# Protoboard_MX2-8-7.net
KiCad netlist of a schematic drawn in EAGLE
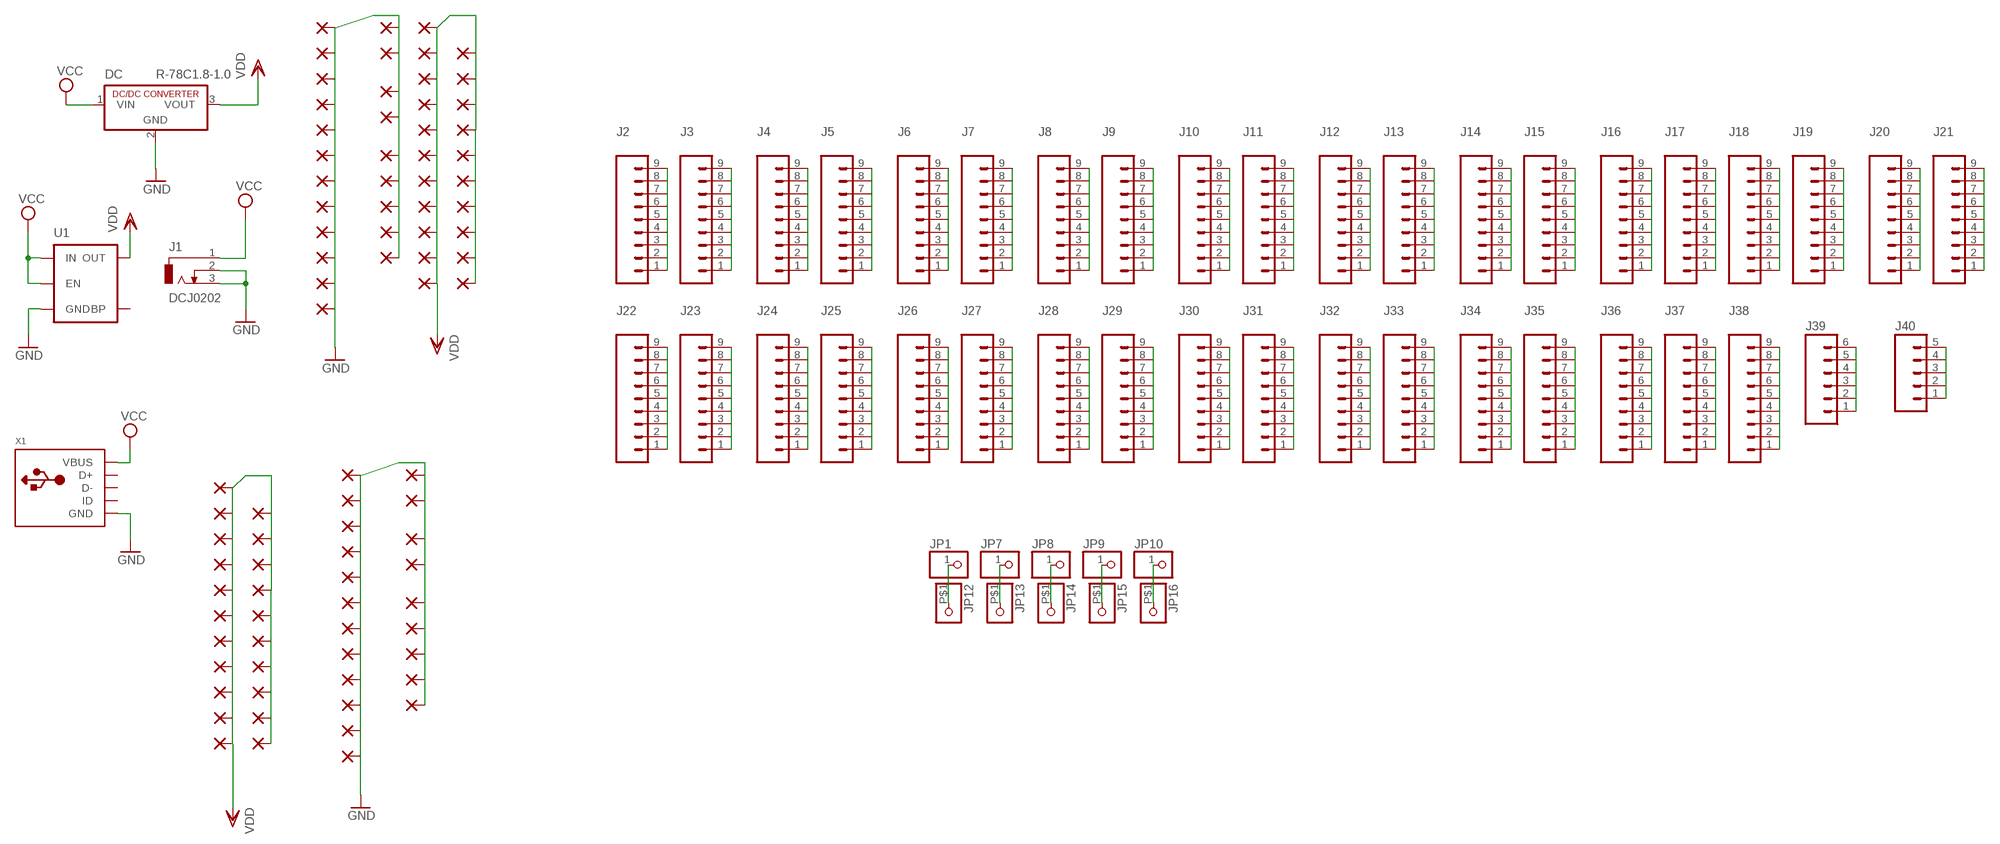
[diagram p0: schematic, sheet 1]

(export (version "E")
  (design (tool "Eeschema 10.0.6"))
  (components
    (comp (ref "DC")
      (value "R-78C1.8-1.0")
      (footprint "eagle-import:SIP3")
      (libsource (lib "eagle-import") (part "R-78C-1.01.8"))
    )
    (comp (ref "J1")
      (value "DCJ0202")
      (footprint "eagle-import:DCJ0202")
      (libsource (lib "eagle-import") (part "DCJ0202"))
    )
    (comp (ref "J2")
      (value "M09NO_SILK")
      (footprint "eagle-import:1X09_NO_SILK")
      (libsource (lib "eagle-import") (part "M09NO_SILK"))
    )
    (comp (ref "J3")
      (value "M09NO_SILK")
      (footprint "eagle-import:1X09_NO_SILK")
      (libsource (lib "eagle-import") (part "M09NO_SILK"))
    )
    (comp (ref "J4")
      (value "M09NO_SILK")
      (footprint "eagle-import:1X09_NO_SILK")
      (libsource (lib "eagle-import") (part "M09NO_SILK"))
    )
    (comp (ref "J5")
      (value "M09NO_SILK")
      (footprint "eagle-import:1X09_NO_SILK")
      (libsource (lib "eagle-import") (part "M09NO_SILK"))
    )
    (comp (ref "J6")
      (value "M09NO_SILK")
      (footprint "eagle-import:1X09_NO_SILK")
      (libsource (lib "eagle-import") (part "M09NO_SILK"))
    )
    (comp (ref "J7")
      (value "M09NO_SILK")
      (footprint "eagle-import:1X09_NO_SILK")
      (libsource (lib "eagle-import") (part "M09NO_SILK"))
    )
    (comp (ref "J8")
      (value "M09NO_SILK")
      (footprint "eagle-import:1X09_NO_SILK")
      (libsource (lib "eagle-import") (part "M09NO_SILK"))
    )
    (comp (ref "J9")
      (value "M09NO_SILK")
      (footprint "eagle-import:1X09_NO_SILK")
      (libsource (lib "eagle-import") (part "M09NO_SILK"))
    )
    (comp (ref "J10")
      (value "M09NO_SILK")
      (footprint "eagle-import:1X09_NO_SILK")
      (libsource (lib "eagle-import") (part "M09NO_SILK"))
    )
    (comp (ref "J11")
      (value "M09NO_SILK")
      (footprint "eagle-import:1X09_NO_SILK")
      (libsource (lib "eagle-import") (part "M09NO_SILK"))
    )
    (comp (ref "J12")
      (value "M09NO_SILK")
      (footprint "eagle-import:1X09_NO_SILK")
      (libsource (lib "eagle-import") (part "M09NO_SILK"))
    )
    (comp (ref "J13")
      (value "M09NO_SILK")
      (footprint "eagle-import:1X09_NO_SILK")
      (libsource (lib "eagle-import") (part "M09NO_SILK"))
    )
    (comp (ref "J14")
      (value "M09NO_SILK")
      (footprint "eagle-import:1X09_NO_SILK")
      (libsource (lib "eagle-import") (part "M09NO_SILK"))
    )
    (comp (ref "J15")
      (value "M09NO_SILK")
      (footprint "eagle-import:1X09_NO_SILK")
      (libsource (lib "eagle-import") (part "M09NO_SILK"))
    )
    (comp (ref "J16")
      (value "M09NO_SILK")
      (footprint "eagle-import:1X09_NO_SILK")
      (libsource (lib "eagle-import") (part "M09NO_SILK"))
    )
    (comp (ref "J17")
      (value "M09NO_SILK")
      (footprint "eagle-import:1X09_NO_SILK")
      (libsource (lib "eagle-import") (part "M09NO_SILK"))
    )
    (comp (ref "J18")
      (value "M09NO_SILK")
      (footprint "eagle-import:1X09_NO_SILK")
      (libsource (lib "eagle-import") (part "M09NO_SILK"))
    )
    (comp (ref "J19")
      (value "M09NO_SILK")
      (footprint "eagle-import:1X09_NO_SILK")
      (libsource (lib "eagle-import") (part "M09NO_SILK"))
    )
    (comp (ref "J20")
      (value "M09NO_SILK")
      (footprint "eagle-import:1X09_NO_SILK")
      (libsource (lib "eagle-import") (part "M09NO_SILK"))
    )
    (comp (ref "J21")
      (value "M09NO_SILK")
      (footprint "eagle-import:1X09_NO_SILK")
      (libsource (lib "eagle-import") (part "M09NO_SILK"))
    )
    (comp (ref "J22")
      (value "M09NO_SILK")
      (footprint "eagle-import:1X09_NO_SILK")
      (libsource (lib "eagle-import") (part "M09NO_SILK"))
    )
    (comp (ref "J23")
      (value "M09NO_SILK")
      (footprint "eagle-import:1X09_NO_SILK")
      (libsource (lib "eagle-import") (part "M09NO_SILK"))
    )
    (comp (ref "J24")
      (value "M09NO_SILK")
      (footprint "eagle-import:1X09_NO_SILK")
      (libsource (lib "eagle-import") (part "M09NO_SILK"))
    )
    (comp (ref "J25")
      (value "M09NO_SILK")
      (footprint "eagle-import:1X09_NO_SILK")
      (libsource (lib "eagle-import") (part "M09NO_SILK"))
    )
    (comp (ref "J26")
      (value "M09NO_SILK")
      (footprint "eagle-import:1X09_NO_SILK")
      (libsource (lib "eagle-import") (part "M09NO_SILK"))
    )
    (comp (ref "J27")
      (value "M09NO_SILK")
      (footprint "eagle-import:1X09_NO_SILK")
      (libsource (lib "eagle-import") (part "M09NO_SILK"))
    )
    (comp (ref "J28")
      (value "M09NO_SILK")
      (footprint "eagle-import:1X09_NO_SILK")
      (libsource (lib "eagle-import") (part "M09NO_SILK"))
    )
    (comp (ref "J29")
      (value "M09NO_SILK")
      (footprint "eagle-import:1X09_NO_SILK")
      (libsource (lib "eagle-import") (part "M09NO_SILK"))
    )
    (comp (ref "J30")
      (value "M09NO_SILK")
      (footprint "eagle-import:1X09_NO_SILK")
      (libsource (lib "eagle-import") (part "M09NO_SILK"))
    )
    (comp (ref "J31")
      (value "M09NO_SILK")
      (footprint "eagle-import:1X09_NO_SILK")
      (libsource (lib "eagle-import") (part "M09NO_SILK"))
    )
    (comp (ref "J32")
      (value "M09NO_SILK")
      (footprint "eagle-import:1X09_NO_SILK")
      (libsource (lib "eagle-import") (part "M09NO_SILK"))
    )
    (comp (ref "J33")
      (value "M09NO_SILK")
      (footprint "eagle-import:1X09_NO_SILK")
      (libsource (lib "eagle-import") (part "M09NO_SILK"))
    )
    (comp (ref "J34")
      (value "M09NO_SILK")
      (footprint "eagle-import:1X09_NO_SILK")
      (libsource (lib "eagle-import") (part "M09NO_SILK"))
    )
    (comp (ref "J35")
      (value "M09NO_SILK")
      (footprint "eagle-import:1X09_NO_SILK")
      (libsource (lib "eagle-import") (part "M09NO_SILK"))
    )
    (comp (ref "J36")
      (value "M09NO_SILK")
      (footprint "eagle-import:1X09_NO_SILK")
      (libsource (lib "eagle-import") (part "M09NO_SILK"))
    )
    (comp (ref "J37")
      (value "M09NO_SILK")
      (footprint "eagle-import:1X09_NO_SILK")
      (libsource (lib "eagle-import") (part "M09NO_SILK"))
    )
    (comp (ref "J38")
      (value "M09NO_SILK")
      (footprint "eagle-import:1X09_NO_SILK")
      (libsource (lib "eagle-import") (part "M09NO_SILK"))
    )
    (comp (ref "J39")
      (value "M06NO_SILK_FEMALE_PTH")
      (footprint "eagle-import:1X06_NO_SILK")
      (libsource (lib "eagle-import") (part "M06NO_SILK_FEMALE_PTH"))
    )
    (comp (ref "J40")
      (value "M05NO_SILK")
      (footprint "eagle-import:1X05_NO_SILK")
      (libsource (lib "eagle-import") (part "M05NO_SILK"))
    )
    (comp (ref "JP1")
      (value "PINHD-1X1CB")
      (footprint "eagle-import:1X01-CLEANBIG")
      (libsource (lib "eagle-import") (part "PINHD-1X1CB"))
    )
    (comp (ref "JP7")
      (value "PINHD-1X1CB")
      (footprint "eagle-import:1X01-CLEANBIG")
      (libsource (lib "eagle-import") (part "PINHD-1X1CB"))
    )
    (comp (ref "JP8")
      (value "PINHD-1X1CB")
      (footprint "eagle-import:1X01-CLEANBIG")
      (libsource (lib "eagle-import") (part "PINHD-1X1CB"))
    )
    (comp (ref "JP9")
      (value "PINHD-1X1CB")
      (footprint "eagle-import:1X01-CLEANBIG")
      (libsource (lib "eagle-import") (part "PINHD-1X1CB"))
    )
    (comp (ref "JP10")
      (value "PINHD-1X1CB")
      (footprint "eagle-import:1X01-CLEANBIG")
      (libsource (lib "eagle-import") (part "PINHD-1X1CB"))
    )
    (comp (ref "JP12")
      (value "PINHD-1X1-BIGPOGO")
      (footprint "eagle-import:1X1-BIGPOGO")
      (libsource (lib "eagle-import") (part "PINHD-1X1-BIGPOGO"))
    )
    (comp (ref "JP13")
      (value "PINHD-1X1-BIGPOGO")
      (footprint "eagle-import:1X1-BIGPOGO")
      (libsource (lib "eagle-import") (part "PINHD-1X1-BIGPOGO"))
    )
    (comp (ref "JP14")
      (value "PINHD-1X1-BIGPOGO")
      (footprint "eagle-import:1X1-BIGPOGO")
      (libsource (lib "eagle-import") (part "PINHD-1X1-BIGPOGO"))
    )
    (comp (ref "JP15")
      (value "PINHD-1X1-BIGPOGO")
      (footprint "eagle-import:1X1-BIGPOGO")
      (libsource (lib "eagle-import") (part "PINHD-1X1-BIGPOGO"))
    )
    (comp (ref "JP16")
      (value "PINHD-1X1-BIGPOGO")
      (footprint "eagle-import:1X1-BIGPOGO")
      (libsource (lib "eagle-import") (part "PINHD-1X1-BIGPOGO"))
    )
    (comp (ref "PAD1")
      (value "1,6/0,8")
      (footprint "eagle-import:1,6_0,8")
      (libsource (lib "eagle-import") (part "1,6/0,8"))
    )
    (comp (ref "PAD2")
      (value "1,6/0,8")
      (footprint "eagle-import:1,6_0,8")
      (libsource (lib "eagle-import") (part "1,6/0,8"))
    )
    (comp (ref "PAD3")
      (value "1,6/0,8")
      (footprint "eagle-import:1,6_0,8")
      (libsource (lib "eagle-import") (part "1,6/0,8"))
    )
    (comp (ref "PAD4")
      (value "1,6/0,8")
      (footprint "eagle-import:1,6_0,8")
      (libsource (lib "eagle-import") (part "1,6/0,8"))
    )
    (comp (ref "PAD5")
      (value "1,6/0,8")
      (footprint "eagle-import:1,6_0,8")
      (libsource (lib "eagle-import") (part "1,6/0,8"))
    )
    (comp (ref "PAD6")
      (value "1,6/0,8")
      (footprint "eagle-import:1,6_0,8")
      (libsource (lib "eagle-import") (part "1,6/0,8"))
    )
    (comp (ref "PAD7")
      (value "1,6/0,8")
      (footprint "eagle-import:1,6_0,8")
      (libsource (lib "eagle-import") (part "1,6/0,8"))
    )
    (comp (ref "PAD8")
      (value "1,6/0,8")
      (footprint "eagle-import:1,6_0,8")
      (libsource (lib "eagle-import") (part "1,6/0,8"))
    )
    (comp (ref "PAD9")
      (value "1,6/0,8")
      (footprint "eagle-import:1,6_0,8")
      (libsource (lib "eagle-import") (part "1,6/0,8"))
    )
    (comp (ref "PAD10")
      (value "1,6/0,8")
      (footprint "eagle-import:1,6_0,8")
      (libsource (lib "eagle-import") (part "1,6/0,8"))
    )
    (comp (ref "PAD11")
      (value "1,6/0,8")
      (footprint "eagle-import:1,6_0,8")
      (libsource (lib "eagle-import") (part "1,6/0,8"))
    )
    (comp (ref "PAD12")
      (value "1,6/0,8")
      (footprint "eagle-import:1,6_0,8")
      (libsource (lib "eagle-import") (part "1,6/0,8"))
    )
    (comp (ref "PAD13")
      (value "1,6/0,8")
      (footprint "eagle-import:1,6_0,8")
      (libsource (lib "eagle-import") (part "1,6/0,8"))
    )
    (comp (ref "PAD14")
      (value "1,6/0,8")
      (footprint "eagle-import:1,6_0,8")
      (libsource (lib "eagle-import") (part "1,6/0,8"))
    )
    (comp (ref "PAD15")
      (value "1,6/0,8")
      (footprint "eagle-import:1,6_0,8")
      (libsource (lib "eagle-import") (part "1,6/0,8"))
    )
    (comp (ref "PAD16")
      (value "1,6/0,8")
      (footprint "eagle-import:1,6_0,8")
      (libsource (lib "eagle-import") (part "1,6/0,8"))
    )
    (comp (ref "PAD17")
      (value "1,6/0,8")
      (footprint "eagle-import:1,6_0,8")
      (libsource (lib "eagle-import") (part "1,6/0,8"))
    )
    (comp (ref "PAD18")
      (value "1,6/0,8")
      (footprint "eagle-import:1,6_0,8")
      (libsource (lib "eagle-import") (part "1,6/0,8"))
    )
    (comp (ref "PAD19")
      (value "1,6/0,8")
      (footprint "eagle-import:1,6_0,8")
      (libsource (lib "eagle-import") (part "1,6/0,8"))
    )
    (comp (ref "PAD22")
      (value "1,6/0,8")
      (footprint "eagle-import:1,6_0,8")
      (libsource (lib "eagle-import") (part "1,6/0,8"))
    )
    (comp (ref "PAD23")
      (value "1,6/0,8")
      (footprint "eagle-import:1,6_0,8")
      (libsource (lib "eagle-import") (part "1,6/0,8"))
    )
    (comp (ref "PAD24")
      (value "1,6/0,8")
      (footprint "eagle-import:1,6_0,8")
      (libsource (lib "eagle-import") (part "1,6/0,8"))
    )
    (comp (ref "PAD25")
      (value "1,6/0,8")
      (footprint "eagle-import:1,6_0,8")
      (libsource (lib "eagle-import") (part "1,6/0,8"))
    )
    (comp (ref "PAD26")
      (value "1,6/0,8")
      (footprint "eagle-import:1,6_0,8")
      (libsource (lib "eagle-import") (part "1,6/0,8"))
    )
    (comp (ref "PAD27")
      (value "1,6/0,8")
      (footprint "eagle-import:1,6_0,8")
      (libsource (lib "eagle-import") (part "1,6/0,8"))
    )
    (comp (ref "PAD28")
      (value "1,6/0,8")
      (footprint "eagle-import:1,6_0,8")
      (libsource (lib "eagle-import") (part "1,6/0,8"))
    )
    (comp (ref "PAD29")
      (value "1,6/0,8")
      (footprint "eagle-import:1,6_0,8")
      (libsource (lib "eagle-import") (part "1,6/0,8"))
    )
    (comp (ref "PAD30")
      (value "1,6/0,8")
      (footprint "eagle-import:1,6_0,8")
      (libsource (lib "eagle-import") (part "1,6/0,8"))
    )
    (comp (ref "PAD31")
      (value "1,6/0,8")
      (footprint "eagle-import:1,6_0,8")
      (libsource (lib "eagle-import") (part "1,6/0,8"))
    )
    (comp (ref "PAD32")
      (value "1,6/0,8")
      (footprint "eagle-import:1,6_0,8")
      (libsource (lib "eagle-import") (part "1,6/0,8"))
    )
    (comp (ref "PAD33")
      (value "1,6/0,8")
      (footprint "eagle-import:1,6_0,8")
      (libsource (lib "eagle-import") (part "1,6/0,8"))
    )
    (comp (ref "PAD34")
      (value "1,6/0,8")
      (footprint "eagle-import:1,6_0,8")
      (libsource (lib "eagle-import") (part "1,6/0,8"))
    )
    (comp (ref "PAD35")
      (value "1,6/0,8")
      (footprint "eagle-import:1,6_0,8")
      (libsource (lib "eagle-import") (part "1,6/0,8"))
    )
    (comp (ref "PAD36")
      (value "1,6/0,8")
      (footprint "eagle-import:1,6_0,8")
      (libsource (lib "eagle-import") (part "1,6/0,8"))
    )
    (comp (ref "PAD37")
      (value "1,6/0,8")
      (footprint "eagle-import:1,6_0,8")
      (libsource (lib "eagle-import") (part "1,6/0,8"))
    )
    (comp (ref "PAD39")
      (value "1,6/0,8")
      (footprint "eagle-import:1,6_0,8")
      (libsource (lib "eagle-import") (part "1,6/0,8"))
    )
    (comp (ref "PAD40")
      (value "1,6/0,8")
      (footprint "eagle-import:1,6_0,8")
      (libsource (lib "eagle-import") (part "1,6/0,8"))
    )
    (comp (ref "PAD41")
      (value "1,6/0,8")
      (footprint "eagle-import:1,6_0,8")
      (libsource (lib "eagle-import") (part "1,6/0,8"))
    )
    (comp (ref "PAD43")
      (value "1,6/0,8")
      (footprint "eagle-import:1,6_0,8")
      (libsource (lib "eagle-import") (part "1,6/0,8"))
    )
    (comp (ref "PAD44")
      (value "1,6/0,8")
      (footprint "eagle-import:1,6_0,8")
      (libsource (lib "eagle-import") (part "1,6/0,8"))
    )
    (comp (ref "PAD45")
      (value "1,6/0,8")
      (footprint "eagle-import:1,6_0,8")
      (libsource (lib "eagle-import") (part "1,6/0,8"))
    )
    (comp (ref "PAD46")
      (value "1,6/0,8")
      (footprint "eagle-import:1,6_0,8")
      (libsource (lib "eagle-import") (part "1,6/0,8"))
    )
    (comp (ref "PAD421")
      (value "1,6/0,8")
      (footprint "eagle-import:1,6_0,8")
      (libsource (lib "eagle-import") (part "1,6/0,8"))
    )
    (comp (ref "PAD422")
      (value "1,6/0,8")
      (footprint "eagle-import:1,6_0,8")
      (libsource (lib "eagle-import") (part "1,6/0,8"))
    )
    (comp (ref "PAD423")
      (value "1,6/0,8")
      (footprint "eagle-import:1,6_0,8")
      (libsource (lib "eagle-import") (part "1,6/0,8"))
    )
    (comp (ref "PAD424")
      (value "1,6/0,8")
      (footprint "eagle-import:1,6_0,8")
      (libsource (lib "eagle-import") (part "1,6/0,8"))
    )
    (comp (ref "PAD425")
      (value "1,6/0,8")
      (footprint "eagle-import:1,6_0,8")
      (libsource (lib "eagle-import") (part "1,6/0,8"))
    )
    (comp (ref "PAD426")
      (value "1,6/0,8")
      (footprint "eagle-import:1,6_0,8")
      (libsource (lib "eagle-import") (part "1,6/0,8"))
    )
    (comp (ref "PAD427")
      (value "1,6/0,8")
      (footprint "eagle-import:1,6_0,8")
      (libsource (lib "eagle-import") (part "1,6/0,8"))
    )
    (comp (ref "PAD428")
      (value "1,6/0,8")
      (footprint "eagle-import:1,6_0,8")
      (libsource (lib "eagle-import") (part "1,6/0,8"))
    )
    (comp (ref "PAD429")
      (value "1,6/0,8")
      (footprint "eagle-import:1,6_0,8")
      (libsource (lib "eagle-import") (part "1,6/0,8"))
    )
    (comp (ref "PAD430")
      (value "1,6/0,8")
      (footprint "eagle-import:1,6_0,8")
      (libsource (lib "eagle-import") (part "1,6/0,8"))
    )
    (comp (ref "PAD431")
      (value "1,6/0,8")
      (footprint "eagle-import:1,6_0,8")
      (libsource (lib "eagle-import") (part "1,6/0,8"))
    )
    (comp (ref "PAD432")
      (value "1,6/0,8")
      (footprint "eagle-import:1,6_0,8")
      (libsource (lib "eagle-import") (part "1,6/0,8"))
    )
    (comp (ref "PAD433")
      (value "1,6/0,8")
      (footprint "eagle-import:1,6_0,8")
      (libsource (lib "eagle-import") (part "1,6/0,8"))
    )
    (comp (ref "PAD434")
      (value "1,6/0,8")
      (footprint "eagle-import:1,6_0,8")
      (libsource (lib "eagle-import") (part "1,6/0,8"))
    )
    (comp (ref "PAD435")
      (value "1,6/0,8")
      (footprint "eagle-import:1,6_0,8")
      (libsource (lib "eagle-import") (part "1,6/0,8"))
    )
    (comp (ref "PAD436")
      (value "1,6/0,8")
      (footprint "eagle-import:1,6_0,8")
      (libsource (lib "eagle-import") (part "1,6/0,8"))
    )
    (comp (ref "PAD437")
      (value "1,6/0,8")
      (footprint "eagle-import:1,6_0,8")
      (libsource (lib "eagle-import") (part "1,6/0,8"))
    )
    (comp (ref "PAD438")
      (value "1,6/0,8")
      (footprint "eagle-import:1,6_0,8")
      (libsource (lib "eagle-import") (part "1,6/0,8"))
    )
    (comp (ref "PAD439")
      (value "1,6/0,8")
      (footprint "eagle-import:1,6_0,8")
      (libsource (lib "eagle-import") (part "1,6/0,8"))
    )
    (comp (ref "PAD440")
      (value "1,6/0,8")
      (footprint "eagle-import:1,6_0,8")
      (libsource (lib "eagle-import") (part "1,6/0,8"))
    )
    (comp (ref "PAD441")
      (value "1,6/0,8")
      (footprint "eagle-import:1,6_0,8")
      (libsource (lib "eagle-import") (part "1,6/0,8"))
    )
    (comp (ref "PAD442")
      (value "1,6/0,8")
      (footprint "eagle-import:1,6_0,8")
      (libsource (lib "eagle-import") (part "1,6/0,8"))
    )
    (comp (ref "PAD443")
      (value "1,6/0,8")
      (footprint "eagle-import:1,6_0,8")
      (libsource (lib "eagle-import") (part "1,6/0,8"))
    )
    (comp (ref "PAD444")
      (value "1,6/0,8")
      (footprint "eagle-import:1,6_0,8")
      (libsource (lib "eagle-import") (part "1,6/0,8"))
    )
    (comp (ref "PAD445")
      (value "1,6/0,8")
      (footprint "eagle-import:1,6_0,8")
      (libsource (lib "eagle-import") (part "1,6/0,8"))
    )
    (comp (ref "PAD446")
      (value "1,6/0,8")
      (footprint "eagle-import:1,6_0,8")
      (libsource (lib "eagle-import") (part "1,6/0,8"))
    )
    (comp (ref "PAD447")
      (value "1,6/0,8")
      (footprint "eagle-import:1,6_0,8")
      (libsource (lib "eagle-import") (part "1,6/0,8"))
    )
    (comp (ref "PAD448")
      (value "1,6/0,8")
      (footprint "eagle-import:1,6_0,8")
      (libsource (lib "eagle-import") (part "1,6/0,8"))
    )
    (comp (ref "PAD449")
      (value "1,6/0,8")
      (footprint "eagle-import:1,6_0,8")
      (libsource (lib "eagle-import") (part "1,6/0,8"))
    )
    (comp (ref "PAD450")
      (value "1,6/0,8")
      (footprint "eagle-import:1,6_0,8")
      (libsource (lib "eagle-import") (part "1,6/0,8"))
    )
    (comp (ref "PAD451")
      (value "1,6/0,8")
      (footprint "eagle-import:1,6_0,8")
      (libsource (lib "eagle-import") (part "1,6/0,8"))
    )
    (comp (ref "PAD452")
      (value "1,6/0,8")
      (footprint "eagle-import:1,6_0,8")
      (libsource (lib "eagle-import") (part "1,6/0,8"))
    )
    (comp (ref "PAD453")
      (value "1,6/0,8")
      (footprint "eagle-import:1,6_0,8")
      (libsource (lib "eagle-import") (part "1,6/0,8"))
    )
    (comp (ref "PAD454")
      (value "1,6/0,8")
      (footprint "eagle-import:1,6_0,8")
      (libsource (lib "eagle-import") (part "1,6/0,8"))
    )
    (comp (ref "PAD455")
      (value "1,6/0,8")
      (footprint "eagle-import:1,6_0,8")
      (libsource (lib "eagle-import") (part "1,6/0,8"))
    )
    (comp (ref "PAD456")
      (value "1,6/0,8")
      (footprint "eagle-import:1,6_0,8")
      (libsource (lib "eagle-import") (part "1,6/0,8"))
    )
    (comp (ref "PAD457")
      (value "1,6/0,8")
      (footprint "eagle-import:1,6_0,8")
      (libsource (lib "eagle-import") (part "1,6/0,8"))
    )
    (comp (ref "PAD458")
      (value "1,6/0,8")
      (footprint "eagle-import:1,6_0,8")
      (libsource (lib "eagle-import") (part "1,6/0,8"))
    )
    (comp (ref "PAD459")
      (value "1,6/0,8")
      (footprint "eagle-import:1,6_0,8")
      (libsource (lib "eagle-import") (part "1,6/0,8"))
    )
    (comp (ref "PAD460")
      (value "1,6/0,8")
      (footprint "eagle-import:1,6_0,8")
      (libsource (lib "eagle-import") (part "1,6/0,8"))
    )
    (comp (ref "PAD461")
      (value "1,6/0,8")
      (footprint "eagle-import:1,6_0,8")
      (libsource (lib "eagle-import") (part "1,6/0,8"))
    )
    (comp (ref "PAD462")
      (value "1,6/0,8")
      (footprint "eagle-import:1,6_0,8")
      (libsource (lib "eagle-import") (part "1,6/0,8"))
    )
    (comp (ref "U1")
      (value "MIC52053.3V")
      (footprint "eagle-import:SOT23-5")
      (libsource (lib "eagle-import") (part "MIC52053.3V"))
    )
    (comp (ref "X1")
      (value "USB_MICRO_20329_V2")
      (footprint "eagle-import:4UCONN_20329_V2")
      (libsource (lib "eagle-import") (part "USB_MICRO_20329_V2"))
    )
  )
  (nets
    (net (code "1") (name "GND") (class "Default")
      (node (ref "DC") (pin "2") (pinfunction "GND_2") (pintype "passive"))
      (node (ref "J1") (pin "2") (pinfunction "2_2") (pintype "passive"))
      (node (ref "J1") (pin "3") (pinfunction "3_3") (pintype "passive"))
      (node (ref "PAD1") (pin "1") (pinfunction "P_1") (pintype "passive"))
      (node (ref "PAD10") (pin "1") (pinfunction "P_1") (pintype "passive"))
      (node (ref "PAD11") (pin "1") (pinfunction "P_1") (pintype "passive"))
      (node (ref "PAD12") (pin "1") (pinfunction "P_1") (pintype "passive"))
      (node (ref "PAD13") (pin "1") (pinfunction "P_1") (pintype "passive"))
      (node (ref "PAD14") (pin "1") (pinfunction "P_1") (pintype "passive"))
      (node (ref "PAD16") (pin "1") (pinfunction "P_1") (pintype "passive"))
      (node (ref "PAD17") (pin "1") (pinfunction "P_1") (pintype "passive"))
      (node (ref "PAD18") (pin "1") (pinfunction "P_1") (pintype "passive"))
      (node (ref "PAD19") (pin "1") (pinfunction "P_1") (pintype "passive"))
      (node (ref "PAD2") (pin "1") (pinfunction "P_1") (pintype "passive"))
      (node (ref "PAD22") (pin "1") (pinfunction "P_1") (pintype "passive"))
      (node (ref "PAD23") (pin "1") (pinfunction "P_1") (pintype "passive"))
      (node (ref "PAD24") (pin "1") (pinfunction "P_1") (pintype "passive"))
      (node (ref "PAD3") (pin "1") (pinfunction "P_1") (pintype "passive"))
      (node (ref "PAD4") (pin "1") (pinfunction "P_1") (pintype "passive"))
      (node (ref "PAD421") (pin "1") (pinfunction "P_1") (pintype "passive"))
      (node (ref "PAD422") (pin "1") (pinfunction "P_1") (pintype "passive"))
      (node (ref "PAD423") (pin "1") (pinfunction "P_1") (pintype "passive"))
      (node (ref "PAD424") (pin "1") (pinfunction "P_1") (pintype "passive"))
      (node (ref "PAD425") (pin "1") (pinfunction "P_1") (pintype "passive"))
      (node (ref "PAD426") (pin "1") (pinfunction "P_1") (pintype "passive"))
      (node (ref "PAD427") (pin "1") (pinfunction "P_1") (pintype "passive"))
      (node (ref "PAD428") (pin "1") (pinfunction "P_1") (pintype "passive"))
      (node (ref "PAD429") (pin "1") (pinfunction "P_1") (pintype "passive"))
      (node (ref "PAD430") (pin "1") (pinfunction "P_1") (pintype "passive"))
      (node (ref "PAD431") (pin "1") (pinfunction "P_1") (pintype "passive"))
      (node (ref "PAD432") (pin "1") (pinfunction "P_1") (pintype "passive"))
      (node (ref "PAD433") (pin "1") (pinfunction "P_1") (pintype "passive"))
      (node (ref "PAD434") (pin "1") (pinfunction "P_1") (pintype "passive"))
      (node (ref "PAD435") (pin "1") (pinfunction "P_1") (pintype "passive"))
      (node (ref "PAD436") (pin "1") (pinfunction "P_1") (pintype "passive"))
      (node (ref "PAD437") (pin "1") (pinfunction "P_1") (pintype "passive"))
      (node (ref "PAD438") (pin "1") (pinfunction "P_1") (pintype "passive"))
      (node (ref "PAD439") (pin "1") (pinfunction "P_1") (pintype "passive"))
      (node (ref "PAD440") (pin "1") (pinfunction "P_1") (pintype "passive"))
      (node (ref "PAD441") (pin "1") (pinfunction "P_1") (pintype "passive"))
      (node (ref "PAD5") (pin "1") (pinfunction "P_1") (pintype "passive"))
      (node (ref "PAD6") (pin "1") (pinfunction "P_1") (pintype "passive"))
      (node (ref "PAD7") (pin "1") (pinfunction "P_1") (pintype "passive"))
      (node (ref "PAD8") (pin "1") (pinfunction "P_1") (pintype "passive"))
      (node (ref "PAD9") (pin "1") (pinfunction "P_1") (pintype "passive"))
      (node (ref "U1") (pin "2") (pinfunction "GND_2") (pintype "input"))
      (node (ref "X1") (pin "BASE@1") (pinfunction "GND_BASE@1") (pintype "power_in"))
      (node (ref "X1") (pin "BASE@2") (pinfunction "GND_BASE@2") (pintype "power_in"))
      (node (ref "X1") (pin "GND") (pinfunction "GND_GND") (pintype "power_in"))
      (node (ref "X1") (pin "SPRT@1") (pinfunction "GND_SPRT@1") (pintype "power_in"))
      (node (ref "X1") (pin "SPRT@2") (pinfunction "GND_SPRT@2") (pintype "power_in"))
      (node (ref "X1") (pin "SPRT@3") (pinfunction "GND_SPRT@3") (pintype "power_in"))
      (node (ref "X1") (pin "SPRT@4") (pinfunction "GND_SPRT@4") (pintype "power_in"))
    )
    (net (code "2") (name "Net-(J2-Pad1)") (class "Default")
      (node (ref "J2") (pin "1") (pinfunction "1_1") (pintype "passive"))
      (node (ref "J2") (pin "2") (pinfunction "2_2") (pintype "passive"))
      (node (ref "J2") (pin "3") (pinfunction "3_3") (pintype "passive"))
      (node (ref "J2") (pin "4") (pinfunction "4_4") (pintype "passive"))
      (node (ref "J2") (pin "5") (pinfunction "5_5") (pintype "passive"))
      (node (ref "J2") (pin "6") (pinfunction "6_6") (pintype "passive"))
      (node (ref "J2") (pin "7") (pinfunction "7_7") (pintype "passive"))
      (node (ref "J2") (pin "8") (pinfunction "8_8") (pintype "passive"))
      (node (ref "J2") (pin "9") (pinfunction "9_9") (pintype "passive"))
    )
    (net (code "3") (name "Net-(J3-Pad1)") (class "Default")
      (node (ref "J3") (pin "1") (pinfunction "1_1") (pintype "passive"))
      (node (ref "J3") (pin "2") (pinfunction "2_2") (pintype "passive"))
      (node (ref "J3") (pin "3") (pinfunction "3_3") (pintype "passive"))
      (node (ref "J3") (pin "4") (pinfunction "4_4") (pintype "passive"))
      (node (ref "J3") (pin "5") (pinfunction "5_5") (pintype "passive"))
      (node (ref "J3") (pin "6") (pinfunction "6_6") (pintype "passive"))
      (node (ref "J3") (pin "7") (pinfunction "7_7") (pintype "passive"))
      (node (ref "J3") (pin "8") (pinfunction "8_8") (pintype "passive"))
      (node (ref "J3") (pin "9") (pinfunction "9_9") (pintype "passive"))
    )
    (net (code "4") (name "Net-(J4-Pad1)") (class "Default")
      (node (ref "J4") (pin "1") (pinfunction "1_1") (pintype "passive"))
      (node (ref "J4") (pin "2") (pinfunction "2_2") (pintype "passive"))
      (node (ref "J4") (pin "3") (pinfunction "3_3") (pintype "passive"))
      (node (ref "J4") (pin "4") (pinfunction "4_4") (pintype "passive"))
      (node (ref "J4") (pin "5") (pinfunction "5_5") (pintype "passive"))
      (node (ref "J4") (pin "6") (pinfunction "6_6") (pintype "passive"))
      (node (ref "J4") (pin "7") (pinfunction "7_7") (pintype "passive"))
      (node (ref "J4") (pin "8") (pinfunction "8_8") (pintype "passive"))
      (node (ref "J4") (pin "9") (pinfunction "9_9") (pintype "passive"))
    )
    (net (code "5") (name "Net-(J5-Pad1)") (class "Default")
      (node (ref "J5") (pin "1") (pinfunction "1_1") (pintype "passive"))
      (node (ref "J5") (pin "2") (pinfunction "2_2") (pintype "passive"))
      (node (ref "J5") (pin "3") (pinfunction "3_3") (pintype "passive"))
      (node (ref "J5") (pin "4") (pinfunction "4_4") (pintype "passive"))
      (node (ref "J5") (pin "5") (pinfunction "5_5") (pintype "passive"))
      (node (ref "J5") (pin "6") (pinfunction "6_6") (pintype "passive"))
      (node (ref "J5") (pin "7") (pinfunction "7_7") (pintype "passive"))
      (node (ref "J5") (pin "8") (pinfunction "8_8") (pintype "passive"))
      (node (ref "J5") (pin "9") (pinfunction "9_9") (pintype "passive"))
    )
    (net (code "6") (name "Net-(J6-Pad1)") (class "Default")
      (node (ref "J6") (pin "1") (pinfunction "1_1") (pintype "passive"))
      (node (ref "J6") (pin "2") (pinfunction "2_2") (pintype "passive"))
      (node (ref "J6") (pin "3") (pinfunction "3_3") (pintype "passive"))
      (node (ref "J6") (pin "4") (pinfunction "4_4") (pintype "passive"))
      (node (ref "J6") (pin "5") (pinfunction "5_5") (pintype "passive"))
      (node (ref "J6") (pin "6") (pinfunction "6_6") (pintype "passive"))
      (node (ref "J6") (pin "7") (pinfunction "7_7") (pintype "passive"))
      (node (ref "J6") (pin "8") (pinfunction "8_8") (pintype "passive"))
      (node (ref "J6") (pin "9") (pinfunction "9_9") (pintype "passive"))
    )
    (net (code "7") (name "Net-(J7-Pad1)") (class "Default")
      (node (ref "J7") (pin "1") (pinfunction "1_1") (pintype "passive"))
      (node (ref "J7") (pin "2") (pinfunction "2_2") (pintype "passive"))
      (node (ref "J7") (pin "3") (pinfunction "3_3") (pintype "passive"))
      (node (ref "J7") (pin "4") (pinfunction "4_4") (pintype "passive"))
      (node (ref "J7") (pin "5") (pinfunction "5_5") (pintype "passive"))
      (node (ref "J7") (pin "6") (pinfunction "6_6") (pintype "passive"))
      (node (ref "J7") (pin "7") (pinfunction "7_7") (pintype "passive"))
      (node (ref "J7") (pin "8") (pinfunction "8_8") (pintype "passive"))
      (node (ref "J7") (pin "9") (pinfunction "9_9") (pintype "passive"))
    )
    (net (code "8") (name "Net-(J8-Pad1)") (class "Default")
      (node (ref "J8") (pin "1") (pinfunction "1_1") (pintype "passive"))
      (node (ref "J8") (pin "2") (pinfunction "2_2") (pintype "passive"))
      (node (ref "J8") (pin "3") (pinfunction "3_3") (pintype "passive"))
      (node (ref "J8") (pin "4") (pinfunction "4_4") (pintype "passive"))
      (node (ref "J8") (pin "5") (pinfunction "5_5") (pintype "passive"))
      (node (ref "J8") (pin "6") (pinfunction "6_6") (pintype "passive"))
      (node (ref "J8") (pin "7") (pinfunction "7_7") (pintype "passive"))
      (node (ref "J8") (pin "8") (pinfunction "8_8") (pintype "passive"))
      (node (ref "J8") (pin "9") (pinfunction "9_9") (pintype "passive"))
    )
    (net (code "9") (name "Net-(J9-Pad1)") (class "Default")
      (node (ref "J9") (pin "1") (pinfunction "1_1") (pintype "passive"))
      (node (ref "J9") (pin "2") (pinfunction "2_2") (pintype "passive"))
      (node (ref "J9") (pin "3") (pinfunction "3_3") (pintype "passive"))
      (node (ref "J9") (pin "4") (pinfunction "4_4") (pintype "passive"))
      (node (ref "J9") (pin "5") (pinfunction "5_5") (pintype "passive"))
      (node (ref "J9") (pin "6") (pinfunction "6_6") (pintype "passive"))
      (node (ref "J9") (pin "7") (pinfunction "7_7") (pintype "passive"))
      (node (ref "J9") (pin "8") (pinfunction "8_8") (pintype "passive"))
      (node (ref "J9") (pin "9") (pinfunction "9_9") (pintype "passive"))
    )
    (net (code "10") (name "Net-(J10-Pad1)") (class "Default")
      (node (ref "J10") (pin "1") (pinfunction "1_1") (pintype "passive"))
      (node (ref "J10") (pin "2") (pinfunction "2_2") (pintype "passive"))
      (node (ref "J10") (pin "3") (pinfunction "3_3") (pintype "passive"))
      (node (ref "J10") (pin "4") (pinfunction "4_4") (pintype "passive"))
      (node (ref "J10") (pin "5") (pinfunction "5_5") (pintype "passive"))
      (node (ref "J10") (pin "6") (pinfunction "6_6") (pintype "passive"))
      (node (ref "J10") (pin "7") (pinfunction "7_7") (pintype "passive"))
      (node (ref "J10") (pin "8") (pinfunction "8_8") (pintype "passive"))
      (node (ref "J10") (pin "9") (pinfunction "9_9") (pintype "passive"))
    )
    (net (code "11") (name "Net-(J11-Pad1)") (class "Default")
      (node (ref "J11") (pin "1") (pinfunction "1_1") (pintype "passive"))
      (node (ref "J11") (pin "2") (pinfunction "2_2") (pintype "passive"))
      (node (ref "J11") (pin "3") (pinfunction "3_3") (pintype "passive"))
      (node (ref "J11") (pin "4") (pinfunction "4_4") (pintype "passive"))
      (node (ref "J11") (pin "5") (pinfunction "5_5") (pintype "passive"))
      (node (ref "J11") (pin "6") (pinfunction "6_6") (pintype "passive"))
      (node (ref "J11") (pin "7") (pinfunction "7_7") (pintype "passive"))
      (node (ref "J11") (pin "8") (pinfunction "8_8") (pintype "passive"))
      (node (ref "J11") (pin "9") (pinfunction "9_9") (pintype "passive"))
    )
    (net (code "12") (name "Net-(J12-Pad1)") (class "Default")
      (node (ref "J12") (pin "1") (pinfunction "1_1") (pintype "passive"))
      (node (ref "J12") (pin "2") (pinfunction "2_2") (pintype "passive"))
      (node (ref "J12") (pin "3") (pinfunction "3_3") (pintype "passive"))
      (node (ref "J12") (pin "4") (pinfunction "4_4") (pintype "passive"))
      (node (ref "J12") (pin "5") (pinfunction "5_5") (pintype "passive"))
      (node (ref "J12") (pin "6") (pinfunction "6_6") (pintype "passive"))
      (node (ref "J12") (pin "7") (pinfunction "7_7") (pintype "passive"))
      (node (ref "J12") (pin "8") (pinfunction "8_8") (pintype "passive"))
      (node (ref "J12") (pin "9") (pinfunction "9_9") (pintype "passive"))
    )
    (net (code "13") (name "Net-(J13-Pad1)") (class "Default")
      (node (ref "J13") (pin "1") (pinfunction "1_1") (pintype "passive"))
      (node (ref "J13") (pin "2") (pinfunction "2_2") (pintype "passive"))
      (node (ref "J13") (pin "3") (pinfunction "3_3") (pintype "passive"))
      (node (ref "J13") (pin "4") (pinfunction "4_4") (pintype "passive"))
      (node (ref "J13") (pin "5") (pinfunction "5_5") (pintype "passive"))
      (node (ref "J13") (pin "6") (pinfunction "6_6") (pintype "passive"))
      (node (ref "J13") (pin "7") (pinfunction "7_7") (pintype "passive"))
      (node (ref "J13") (pin "8") (pinfunction "8_8") (pintype "passive"))
      (node (ref "J13") (pin "9") (pinfunction "9_9") (pintype "passive"))
    )
    (net (code "14") (name "Net-(J14-Pad1)") (class "Default")
      (node (ref "J14") (pin "1") (pinfunction "1_1") (pintype "passive"))
      (node (ref "J14") (pin "2") (pinfunction "2_2") (pintype "passive"))
      (node (ref "J14") (pin "3") (pinfunction "3_3") (pintype "passive"))
      (node (ref "J14") (pin "4") (pinfunction "4_4") (pintype "passive"))
      (node (ref "J14") (pin "5") (pinfunction "5_5") (pintype "passive"))
      (node (ref "J14") (pin "6") (pinfunction "6_6") (pintype "passive"))
      (node (ref "J14") (pin "7") (pinfunction "7_7") (pintype "passive"))
      (node (ref "J14") (pin "8") (pinfunction "8_8") (pintype "passive"))
      (node (ref "J14") (pin "9") (pinfunction "9_9") (pintype "passive"))
    )
    (net (code "15") (name "Net-(J15-Pad1)") (class "Default")
      (node (ref "J15") (pin "1") (pinfunction "1_1") (pintype "passive"))
      (node (ref "J15") (pin "2") (pinfunction "2_2") (pintype "passive"))
      (node (ref "J15") (pin "3") (pinfunction "3_3") (pintype "passive"))
      (node (ref "J15") (pin "4") (pinfunction "4_4") (pintype "passive"))
      (node (ref "J15") (pin "5") (pinfunction "5_5") (pintype "passive"))
      (node (ref "J15") (pin "6") (pinfunction "6_6") (pintype "passive"))
      (node (ref "J15") (pin "7") (pinfunction "7_7") (pintype "passive"))
      (node (ref "J15") (pin "8") (pinfunction "8_8") (pintype "passive"))
      (node (ref "J15") (pin "9") (pinfunction "9_9") (pintype "passive"))
    )
    (net (code "16") (name "Net-(J16-Pad1)") (class "Default")
      (node (ref "J16") (pin "1") (pinfunction "1_1") (pintype "passive"))
      (node (ref "J16") (pin "2") (pinfunction "2_2") (pintype "passive"))
      (node (ref "J16") (pin "3") (pinfunction "3_3") (pintype "passive"))
      (node (ref "J16") (pin "4") (pinfunction "4_4") (pintype "passive"))
      (node (ref "J16") (pin "5") (pinfunction "5_5") (pintype "passive"))
      (node (ref "J16") (pin "6") (pinfunction "6_6") (pintype "passive"))
      (node (ref "J16") (pin "7") (pinfunction "7_7") (pintype "passive"))
      (node (ref "J16") (pin "8") (pinfunction "8_8") (pintype "passive"))
      (node (ref "J16") (pin "9") (pinfunction "9_9") (pintype "passive"))
    )
    (net (code "17") (name "Net-(J17-Pad1)") (class "Default")
      (node (ref "J17") (pin "1") (pinfunction "1_1") (pintype "passive"))
      (node (ref "J17") (pin "2") (pinfunction "2_2") (pintype "passive"))
      (node (ref "J17") (pin "3") (pinfunction "3_3") (pintype "passive"))
      (node (ref "J17") (pin "4") (pinfunction "4_4") (pintype "passive"))
      (node (ref "J17") (pin "5") (pinfunction "5_5") (pintype "passive"))
      (node (ref "J17") (pin "6") (pinfunction "6_6") (pintype "passive"))
      (node (ref "J17") (pin "7") (pinfunction "7_7") (pintype "passive"))
      (node (ref "J17") (pin "8") (pinfunction "8_8") (pintype "passive"))
      (node (ref "J17") (pin "9") (pinfunction "9_9") (pintype "passive"))
    )
    (net (code "18") (name "Net-(J18-Pad1)") (class "Default")
      (node (ref "J18") (pin "1") (pinfunction "1_1") (pintype "passive"))
      (node (ref "J18") (pin "2") (pinfunction "2_2") (pintype "passive"))
      (node (ref "J18") (pin "3") (pinfunction "3_3") (pintype "passive"))
      (node (ref "J18") (pin "4") (pinfunction "4_4") (pintype "passive"))
      (node (ref "J18") (pin "5") (pinfunction "5_5") (pintype "passive"))
      (node (ref "J18") (pin "6") (pinfunction "6_6") (pintype "passive"))
      (node (ref "J18") (pin "7") (pinfunction "7_7") (pintype "passive"))
      (node (ref "J18") (pin "8") (pinfunction "8_8") (pintype "passive"))
      (node (ref "J18") (pin "9") (pinfunction "9_9") (pintype "passive"))
    )
    (net (code "19") (name "Net-(J19-Pad1)") (class "Default")
      (node (ref "J19") (pin "1") (pinfunction "1_1") (pintype "passive"))
      (node (ref "J19") (pin "2") (pinfunction "2_2") (pintype "passive"))
      (node (ref "J19") (pin "3") (pinfunction "3_3") (pintype "passive"))
      (node (ref "J19") (pin "4") (pinfunction "4_4") (pintype "passive"))
      (node (ref "J19") (pin "5") (pinfunction "5_5") (pintype "passive"))
      (node (ref "J19") (pin "6") (pinfunction "6_6") (pintype "passive"))
      (node (ref "J19") (pin "7") (pinfunction "7_7") (pintype "passive"))
      (node (ref "J19") (pin "8") (pinfunction "8_8") (pintype "passive"))
      (node (ref "J19") (pin "9") (pinfunction "9_9") (pintype "passive"))
    )
    (net (code "20") (name "Net-(J20-Pad1)") (class "Default")
      (node (ref "J20") (pin "1") (pinfunction "1_1") (pintype "passive"))
      (node (ref "J20") (pin "2") (pinfunction "2_2") (pintype "passive"))
      (node (ref "J20") (pin "3") (pinfunction "3_3") (pintype "passive"))
      (node (ref "J20") (pin "4") (pinfunction "4_4") (pintype "passive"))
      (node (ref "J20") (pin "5") (pinfunction "5_5") (pintype "passive"))
      (node (ref "J20") (pin "6") (pinfunction "6_6") (pintype "passive"))
      (node (ref "J20") (pin "7") (pinfunction "7_7") (pintype "passive"))
      (node (ref "J20") (pin "8") (pinfunction "8_8") (pintype "passive"))
      (node (ref "J20") (pin "9") (pinfunction "9_9") (pintype "passive"))
    )
    (net (code "21") (name "Net-(J21-Pad1)") (class "Default")
      (node (ref "J21") (pin "1") (pinfunction "1_1") (pintype "passive"))
      (node (ref "J21") (pin "2") (pinfunction "2_2") (pintype "passive"))
      (node (ref "J21") (pin "3") (pinfunction "3_3") (pintype "passive"))
      (node (ref "J21") (pin "4") (pinfunction "4_4") (pintype "passive"))
      (node (ref "J21") (pin "5") (pinfunction "5_5") (pintype "passive"))
      (node (ref "J21") (pin "6") (pinfunction "6_6") (pintype "passive"))
      (node (ref "J21") (pin "7") (pinfunction "7_7") (pintype "passive"))
      (node (ref "J21") (pin "8") (pinfunction "8_8") (pintype "passive"))
      (node (ref "J21") (pin "9") (pinfunction "9_9") (pintype "passive"))
    )
    (net (code "22") (name "Net-(J22-Pad1)") (class "Default")
      (node (ref "J22") (pin "1") (pinfunction "1_1") (pintype "passive"))
      (node (ref "J22") (pin "2") (pinfunction "2_2") (pintype "passive"))
      (node (ref "J22") (pin "3") (pinfunction "3_3") (pintype "passive"))
      (node (ref "J22") (pin "4") (pinfunction "4_4") (pintype "passive"))
      (node (ref "J22") (pin "5") (pinfunction "5_5") (pintype "passive"))
      (node (ref "J22") (pin "6") (pinfunction "6_6") (pintype "passive"))
      (node (ref "J22") (pin "7") (pinfunction "7_7") (pintype "passive"))
      (node (ref "J22") (pin "8") (pinfunction "8_8") (pintype "passive"))
      (node (ref "J22") (pin "9") (pinfunction "9_9") (pintype "passive"))
    )
    (net (code "23") (name "Net-(J23-Pad1)") (class "Default")
      (node (ref "J23") (pin "1") (pinfunction "1_1") (pintype "passive"))
      (node (ref "J23") (pin "2") (pinfunction "2_2") (pintype "passive"))
      (node (ref "J23") (pin "3") (pinfunction "3_3") (pintype "passive"))
      (node (ref "J23") (pin "4") (pinfunction "4_4") (pintype "passive"))
      (node (ref "J23") (pin "5") (pinfunction "5_5") (pintype "passive"))
      (node (ref "J23") (pin "6") (pinfunction "6_6") (pintype "passive"))
      (node (ref "J23") (pin "7") (pinfunction "7_7") (pintype "passive"))
      (node (ref "J23") (pin "8") (pinfunction "8_8") (pintype "passive"))
      (node (ref "J23") (pin "9") (pinfunction "9_9") (pintype "passive"))
    )
    (net (code "24") (name "Net-(J24-Pad1)") (class "Default")
      (node (ref "J24") (pin "1") (pinfunction "1_1") (pintype "passive"))
      (node (ref "J24") (pin "2") (pinfunction "2_2") (pintype "passive"))
      (node (ref "J24") (pin "3") (pinfunction "3_3") (pintype "passive"))
      (node (ref "J24") (pin "4") (pinfunction "4_4") (pintype "passive"))
      (node (ref "J24") (pin "5") (pinfunction "5_5") (pintype "passive"))
      (node (ref "J24") (pin "6") (pinfunction "6_6") (pintype "passive"))
      (node (ref "J24") (pin "7") (pinfunction "7_7") (pintype "passive"))
      (node (ref "J24") (pin "8") (pinfunction "8_8") (pintype "passive"))
      (node (ref "J24") (pin "9") (pinfunction "9_9") (pintype "passive"))
    )
    (net (code "25") (name "Net-(J25-Pad1)") (class "Default")
      (node (ref "J25") (pin "1") (pinfunction "1_1") (pintype "passive"))
      (node (ref "J25") (pin "2") (pinfunction "2_2") (pintype "passive"))
      (node (ref "J25") (pin "3") (pinfunction "3_3") (pintype "passive"))
      (node (ref "J25") (pin "4") (pinfunction "4_4") (pintype "passive"))
      (node (ref "J25") (pin "5") (pinfunction "5_5") (pintype "passive"))
      (node (ref "J25") (pin "6") (pinfunction "6_6") (pintype "passive"))
      (node (ref "J25") (pin "7") (pinfunction "7_7") (pintype "passive"))
      (node (ref "J25") (pin "8") (pinfunction "8_8") (pintype "passive"))
      (node (ref "J25") (pin "9") (pinfunction "9_9") (pintype "passive"))
    )
    (net (code "26") (name "Net-(J26-Pad1)") (class "Default")
      (node (ref "J26") (pin "1") (pinfunction "1_1") (pintype "passive"))
      (node (ref "J26") (pin "2") (pinfunction "2_2") (pintype "passive"))
      (node (ref "J26") (pin "3") (pinfunction "3_3") (pintype "passive"))
      (node (ref "J26") (pin "4") (pinfunction "4_4") (pintype "passive"))
      (node (ref "J26") (pin "5") (pinfunction "5_5") (pintype "passive"))
      (node (ref "J26") (pin "6") (pinfunction "6_6") (pintype "passive"))
      (node (ref "J26") (pin "7") (pinfunction "7_7") (pintype "passive"))
      (node (ref "J26") (pin "8") (pinfunction "8_8") (pintype "passive"))
      (node (ref "J26") (pin "9") (pinfunction "9_9") (pintype "passive"))
    )
    (net (code "27") (name "Net-(J27-Pad1)") (class "Default")
      (node (ref "J27") (pin "1") (pinfunction "1_1") (pintype "passive"))
      (node (ref "J27") (pin "2") (pinfunction "2_2") (pintype "passive"))
      (node (ref "J27") (pin "3") (pinfunction "3_3") (pintype "passive"))
      (node (ref "J27") (pin "4") (pinfunction "4_4") (pintype "passive"))
      (node (ref "J27") (pin "5") (pinfunction "5_5") (pintype "passive"))
      (node (ref "J27") (pin "6") (pinfunction "6_6") (pintype "passive"))
      (node (ref "J27") (pin "7") (pinfunction "7_7") (pintype "passive"))
      (node (ref "J27") (pin "8") (pinfunction "8_8") (pintype "passive"))
      (node (ref "J27") (pin "9") (pinfunction "9_9") (pintype "passive"))
    )
    (net (code "28") (name "Net-(J28-Pad1)") (class "Default")
      (node (ref "J28") (pin "1") (pinfunction "1_1") (pintype "passive"))
      (node (ref "J28") (pin "2") (pinfunction "2_2") (pintype "passive"))
      (node (ref "J28") (pin "3") (pinfunction "3_3") (pintype "passive"))
      (node (ref "J28") (pin "4") (pinfunction "4_4") (pintype "passive"))
      (node (ref "J28") (pin "5") (pinfunction "5_5") (pintype "passive"))
      (node (ref "J28") (pin "6") (pinfunction "6_6") (pintype "passive"))
      (node (ref "J28") (pin "7") (pinfunction "7_7") (pintype "passive"))
      (node (ref "J28") (pin "8") (pinfunction "8_8") (pintype "passive"))
      (node (ref "J28") (pin "9") (pinfunction "9_9") (pintype "passive"))
    )
    (net (code "29") (name "Net-(J29-Pad1)") (class "Default")
      (node (ref "J29") (pin "1") (pinfunction "1_1") (pintype "passive"))
      (node (ref "J29") (pin "2") (pinfunction "2_2") (pintype "passive"))
      (node (ref "J29") (pin "3") (pinfunction "3_3") (pintype "passive"))
      (node (ref "J29") (pin "4") (pinfunction "4_4") (pintype "passive"))
      (node (ref "J29") (pin "5") (pinfunction "5_5") (pintype "passive"))
      (node (ref "J29") (pin "6") (pinfunction "6_6") (pintype "passive"))
      (node (ref "J29") (pin "7") (pinfunction "7_7") (pintype "passive"))
      (node (ref "J29") (pin "8") (pinfunction "8_8") (pintype "passive"))
      (node (ref "J29") (pin "9") (pinfunction "9_9") (pintype "passive"))
    )
    (net (code "30") (name "Net-(J30-Pad1)") (class "Default")
      (node (ref "J30") (pin "1") (pinfunction "1_1") (pintype "passive"))
      (node (ref "J30") (pin "2") (pinfunction "2_2") (pintype "passive"))
      (node (ref "J30") (pin "3") (pinfunction "3_3") (pintype "passive"))
      (node (ref "J30") (pin "4") (pinfunction "4_4") (pintype "passive"))
      (node (ref "J30") (pin "5") (pinfunction "5_5") (pintype "passive"))
      (node (ref "J30") (pin "6") (pinfunction "6_6") (pintype "passive"))
      (node (ref "J30") (pin "7") (pinfunction "7_7") (pintype "passive"))
      (node (ref "J30") (pin "8") (pinfunction "8_8") (pintype "passive"))
      (node (ref "J30") (pin "9") (pinfunction "9_9") (pintype "passive"))
    )
    (net (code "31") (name "Net-(J31-Pad1)") (class "Default")
      (node (ref "J31") (pin "1") (pinfunction "1_1") (pintype "passive"))
      (node (ref "J31") (pin "2") (pinfunction "2_2") (pintype "passive"))
      (node (ref "J31") (pin "3") (pinfunction "3_3") (pintype "passive"))
      (node (ref "J31") (pin "4") (pinfunction "4_4") (pintype "passive"))
      (node (ref "J31") (pin "5") (pinfunction "5_5") (pintype "passive"))
      (node (ref "J31") (pin "6") (pinfunction "6_6") (pintype "passive"))
      (node (ref "J31") (pin "7") (pinfunction "7_7") (pintype "passive"))
      (node (ref "J31") (pin "8") (pinfunction "8_8") (pintype "passive"))
      (node (ref "J31") (pin "9") (pinfunction "9_9") (pintype "passive"))
    )
    (net (code "32") (name "Net-(J32-Pad1)") (class "Default")
      (node (ref "J32") (pin "1") (pinfunction "1_1") (pintype "passive"))
      (node (ref "J32") (pin "2") (pinfunction "2_2") (pintype "passive"))
      (node (ref "J32") (pin "3") (pinfunction "3_3") (pintype "passive"))
      (node (ref "J32") (pin "4") (pinfunction "4_4") (pintype "passive"))
      (node (ref "J32") (pin "5") (pinfunction "5_5") (pintype "passive"))
      (node (ref "J32") (pin "6") (pinfunction "6_6") (pintype "passive"))
      (node (ref "J32") (pin "7") (pinfunction "7_7") (pintype "passive"))
      (node (ref "J32") (pin "8") (pinfunction "8_8") (pintype "passive"))
      (node (ref "J32") (pin "9") (pinfunction "9_9") (pintype "passive"))
    )
    (net (code "33") (name "Net-(J33-Pad1)") (class "Default")
      (node (ref "J33") (pin "1") (pinfunction "1_1") (pintype "passive"))
      (node (ref "J33") (pin "2") (pinfunction "2_2") (pintype "passive"))
      (node (ref "J33") (pin "3") (pinfunction "3_3") (pintype "passive"))
      (node (ref "J33") (pin "4") (pinfunction "4_4") (pintype "passive"))
      (node (ref "J33") (pin "5") (pinfunction "5_5") (pintype "passive"))
      (node (ref "J33") (pin "6") (pinfunction "6_6") (pintype "passive"))
      (node (ref "J33") (pin "7") (pinfunction "7_7") (pintype "passive"))
      (node (ref "J33") (pin "8") (pinfunction "8_8") (pintype "passive"))
      (node (ref "J33") (pin "9") (pinfunction "9_9") (pintype "passive"))
    )
    (net (code "34") (name "Net-(J34-Pad1)") (class "Default")
      (node (ref "J34") (pin "1") (pinfunction "1_1") (pintype "passive"))
      (node (ref "J34") (pin "2") (pinfunction "2_2") (pintype "passive"))
      (node (ref "J34") (pin "3") (pinfunction "3_3") (pintype "passive"))
      (node (ref "J34") (pin "4") (pinfunction "4_4") (pintype "passive"))
      (node (ref "J34") (pin "5") (pinfunction "5_5") (pintype "passive"))
      (node (ref "J34") (pin "6") (pinfunction "6_6") (pintype "passive"))
      (node (ref "J34") (pin "7") (pinfunction "7_7") (pintype "passive"))
      (node (ref "J34") (pin "8") (pinfunction "8_8") (pintype "passive"))
      (node (ref "J34") (pin "9") (pinfunction "9_9") (pintype "passive"))
    )
    (net (code "35") (name "Net-(J35-Pad1)") (class "Default")
      (node (ref "J35") (pin "1") (pinfunction "1_1") (pintype "passive"))
      (node (ref "J35") (pin "2") (pinfunction "2_2") (pintype "passive"))
      (node (ref "J35") (pin "3") (pinfunction "3_3") (pintype "passive"))
      (node (ref "J35") (pin "4") (pinfunction "4_4") (pintype "passive"))
      (node (ref "J35") (pin "5") (pinfunction "5_5") (pintype "passive"))
      (node (ref "J35") (pin "6") (pinfunction "6_6") (pintype "passive"))
      (node (ref "J35") (pin "7") (pinfunction "7_7") (pintype "passive"))
      (node (ref "J35") (pin "8") (pinfunction "8_8") (pintype "passive"))
      (node (ref "J35") (pin "9") (pinfunction "9_9") (pintype "passive"))
    )
    (net (code "36") (name "Net-(J36-Pad1)") (class "Default")
      (node (ref "J36") (pin "1") (pinfunction "1_1") (pintype "passive"))
      (node (ref "J36") (pin "2") (pinfunction "2_2") (pintype "passive"))
      (node (ref "J36") (pin "3") (pinfunction "3_3") (pintype "passive"))
      (node (ref "J36") (pin "4") (pinfunction "4_4") (pintype "passive"))
      (node (ref "J36") (pin "5") (pinfunction "5_5") (pintype "passive"))
      (node (ref "J36") (pin "6") (pinfunction "6_6") (pintype "passive"))
      (node (ref "J36") (pin "7") (pinfunction "7_7") (pintype "passive"))
      (node (ref "J36") (pin "8") (pinfunction "8_8") (pintype "passive"))
      (node (ref "J36") (pin "9") (pinfunction "9_9") (pintype "passive"))
    )
    (net (code "37") (name "Net-(J37-Pad1)") (class "Default")
      (node (ref "J37") (pin "1") (pinfunction "1_1") (pintype "passive"))
      (node (ref "J37") (pin "2") (pinfunction "2_2") (pintype "passive"))
      (node (ref "J37") (pin "3") (pinfunction "3_3") (pintype "passive"))
      (node (ref "J37") (pin "4") (pinfunction "4_4") (pintype "passive"))
      (node (ref "J37") (pin "5") (pinfunction "5_5") (pintype "passive"))
      (node (ref "J37") (pin "6") (pinfunction "6_6") (pintype "passive"))
      (node (ref "J37") (pin "7") (pinfunction "7_7") (pintype "passive"))
      (node (ref "J37") (pin "8") (pinfunction "8_8") (pintype "passive"))
      (node (ref "J37") (pin "9") (pinfunction "9_9") (pintype "passive"))
    )
    (net (code "38") (name "Net-(J38-Pad1)") (class "Default")
      (node (ref "J38") (pin "1") (pinfunction "1_1") (pintype "passive"))
      (node (ref "J38") (pin "2") (pinfunction "2_2") (pintype "passive"))
      (node (ref "J38") (pin "3") (pinfunction "3_3") (pintype "passive"))
      (node (ref "J38") (pin "4") (pinfunction "4_4") (pintype "passive"))
      (node (ref "J38") (pin "5") (pinfunction "5_5") (pintype "passive"))
      (node (ref "J38") (pin "6") (pinfunction "6_6") (pintype "passive"))
      (node (ref "J38") (pin "7") (pinfunction "7_7") (pintype "passive"))
      (node (ref "J38") (pin "8") (pinfunction "8_8") (pintype "passive"))
      (node (ref "J38") (pin "9") (pinfunction "9_9") (pintype "passive"))
    )
    (net (code "39") (name "Net-(J39-Pad1)") (class "Default")
      (node (ref "J39") (pin "1") (pinfunction "1_1") (pintype "passive"))
      (node (ref "J39") (pin "2") (pinfunction "2_2") (pintype "passive"))
      (node (ref "J39") (pin "3") (pinfunction "3_3") (pintype "passive"))
      (node (ref "J39") (pin "4") (pinfunction "4_4") (pintype "passive"))
      (node (ref "J39") (pin "5") (pinfunction "5_5") (pintype "passive"))
      (node (ref "J39") (pin "6") (pinfunction "6_6") (pintype "passive"))
    )
    (net (code "40") (name "Net-(J40-Pad1)") (class "Default")
      (node (ref "J40") (pin "1") (pinfunction "1_1") (pintype "passive"))
      (node (ref "J40") (pin "2") (pinfunction "2_2") (pintype "passive"))
      (node (ref "J40") (pin "3") (pinfunction "3_3") (pintype "passive"))
      (node (ref "J40") (pin "4") (pinfunction "4_4") (pintype "passive"))
      (node (ref "J40") (pin "5") (pinfunction "5_5") (pintype "passive"))
    )
    (net (code "41") (name "Net-(JP12-1)") (class "Default")
      (node (ref "JP1") (pin "1") (pinfunction "1_1") (pintype "passive"))
      (node (ref "JP12") (pin "P$1") (pinfunction "1_P$1") (pintype "passive"))
    )
    (net (code "42") (name "Net-(JP13-1)") (class "Default")
      (node (ref "JP13") (pin "P$1") (pinfunction "1_P$1") (pintype "passive"))
      (node (ref "JP7") (pin "1") (pinfunction "1_1") (pintype "passive"))
    )
    (net (code "43") (name "Net-(JP14-1)") (class "Default")
      (node (ref "JP14") (pin "P$1") (pinfunction "1_P$1") (pintype "passive"))
      (node (ref "JP8") (pin "1") (pinfunction "1_1") (pintype "passive"))
    )
    (net (code "44") (name "Net-(JP15-1)") (class "Default")
      (node (ref "JP15") (pin "P$1") (pinfunction "1_P$1") (pintype "passive"))
      (node (ref "JP9") (pin "1") (pinfunction "1_1") (pintype "passive"))
    )
    (net (code "45") (name "Net-(JP16-1)") (class "Default")
      (node (ref "JP10") (pin "1") (pinfunction "1_1") (pintype "passive"))
      (node (ref "JP16") (pin "P$1") (pinfunction "1_P$1") (pintype "passive"))
    )
    (net (code "46") (name "VCC") (class "Default")
      (node (ref "DC") (pin "1") (pinfunction "VIN_1") (pintype "passive"))
      (node (ref "J1") (pin "1") (pinfunction "1_1") (pintype "passive"))
      (node (ref "U1") (pin "1") (pinfunction "IN_1") (pintype "input"))
      (node (ref "U1") (pin "3") (pinfunction "EN_3") (pintype "input"))
      (node (ref "X1") (pin "VBUS") (pinfunction "VBUS_VBUS") (pintype "power_in"))
    )
    (net (code "47") (name "VDD") (class "Default")
      (node (ref "DC") (pin "3") (pinfunction "VOUT_3") (pintype "passive"))
      (node (ref "PAD15") (pin "1") (pinfunction "P_1") (pintype "passive"))
      (node (ref "PAD25") (pin "1") (pinfunction "P_1") (pintype "passive"))
      (node (ref "PAD26") (pin "1") (pinfunction "P_1") (pintype "passive"))
      (node (ref "PAD27") (pin "1") (pinfunction "P_1") (pintype "passive"))
      (node (ref "PAD28") (pin "1") (pinfunction "P_1") (pintype "passive"))
      (node (ref "PAD29") (pin "1") (pinfunction "P_1") (pintype "passive"))
      (node (ref "PAD30") (pin "1") (pinfunction "P_1") (pintype "passive"))
      (node (ref "PAD31") (pin "1") (pinfunction "P_1") (pintype "passive"))
      (node (ref "PAD32") (pin "1") (pinfunction "P_1") (pintype "passive"))
      (node (ref "PAD33") (pin "1") (pinfunction "P_1") (pintype "passive"))
      (node (ref "PAD34") (pin "1") (pinfunction "P_1") (pintype "passive"))
      (node (ref "PAD35") (pin "1") (pinfunction "P_1") (pintype "passive"))
      (node (ref "PAD36") (pin "1") (pinfunction "P_1") (pintype "passive"))
      (node (ref "PAD37") (pin "1") (pinfunction "P_1") (pintype "passive"))
      (node (ref "PAD39") (pin "1") (pinfunction "P_1") (pintype "passive"))
      (node (ref "PAD40") (pin "1") (pinfunction "P_1") (pintype "passive"))
      (node (ref "PAD41") (pin "1") (pinfunction "P_1") (pintype "passive"))
      (node (ref "PAD43") (pin "1") (pinfunction "P_1") (pintype "passive"))
      (node (ref "PAD44") (pin "1") (pinfunction "P_1") (pintype "passive"))
      (node (ref "PAD442") (pin "1") (pinfunction "P_1") (pintype "passive"))
      (node (ref "PAD443") (pin "1") (pinfunction "P_1") (pintype "passive"))
      (node (ref "PAD444") (pin "1") (pinfunction "P_1") (pintype "passive"))
      (node (ref "PAD445") (pin "1") (pinfunction "P_1") (pintype "passive"))
      (node (ref "PAD446") (pin "1") (pinfunction "P_1") (pintype "passive"))
      (node (ref "PAD447") (pin "1") (pinfunction "P_1") (pintype "passive"))
      (node (ref "PAD448") (pin "1") (pinfunction "P_1") (pintype "passive"))
      (node (ref "PAD449") (pin "1") (pinfunction "P_1") (pintype "passive"))
      (node (ref "PAD45") (pin "1") (pinfunction "P_1") (pintype "passive"))
      (node (ref "PAD450") (pin "1") (pinfunction "P_1") (pintype "passive"))
      (node (ref "PAD451") (pin "1") (pinfunction "P_1") (pintype "passive"))
      (node (ref "PAD452") (pin "1") (pinfunction "P_1") (pintype "passive"))
      (node (ref "PAD453") (pin "1") (pinfunction "P_1") (pintype "passive"))
      (node (ref "PAD454") (pin "1") (pinfunction "P_1") (pintype "passive"))
      (node (ref "PAD455") (pin "1") (pinfunction "P_1") (pintype "passive"))
      (node (ref "PAD456") (pin "1") (pinfunction "P_1") (pintype "passive"))
      (node (ref "PAD457") (pin "1") (pinfunction "P_1") (pintype "passive"))
      (node (ref "PAD458") (pin "1") (pinfunction "P_1") (pintype "passive"))
      (node (ref "PAD459") (pin "1") (pinfunction "P_1") (pintype "passive"))
      (node (ref "PAD46") (pin "1") (pinfunction "P_1") (pintype "passive"))
      (node (ref "PAD460") (pin "1") (pinfunction "P_1") (pintype "passive"))
      (node (ref "PAD461") (pin "1") (pinfunction "P_1") (pintype "passive"))
      (node (ref "PAD462") (pin "1") (pinfunction "P_1") (pintype "passive"))
      (node (ref "U1") (pin "5") (pinfunction "OUT_5") (pintype "passive"))
    )
    (net (code "48") (name "unconnected-(U1-BP-Pad4)") (class "Default")
      (node (ref "U1") (pin "4") (pinfunction "BP_4") (pintype "input"))
    )
    (net (code "49") (name "unconnected-(X1-PadD+)") (class "Default")
      (node (ref "X1") (pin "D+") (pinfunction "D+_D+") (pintype "bidirectional"))
    )
    (net (code "50") (name "unconnected-(X1-PadD-)") (class "Default")
      (node (ref "X1") (pin "D-") (pinfunction "D-_D-") (pintype "bidirectional"))
    )
    (net (code "51") (name "unconnected-(X1-PadID)") (class "Default")
      (node (ref "X1") (pin "ID") (pinfunction "ID_ID") (pintype "bidirectional"))
    )
  )
)
